# Microcontroller.net
KiCad netlist of a schematic drawn in Altium Designer
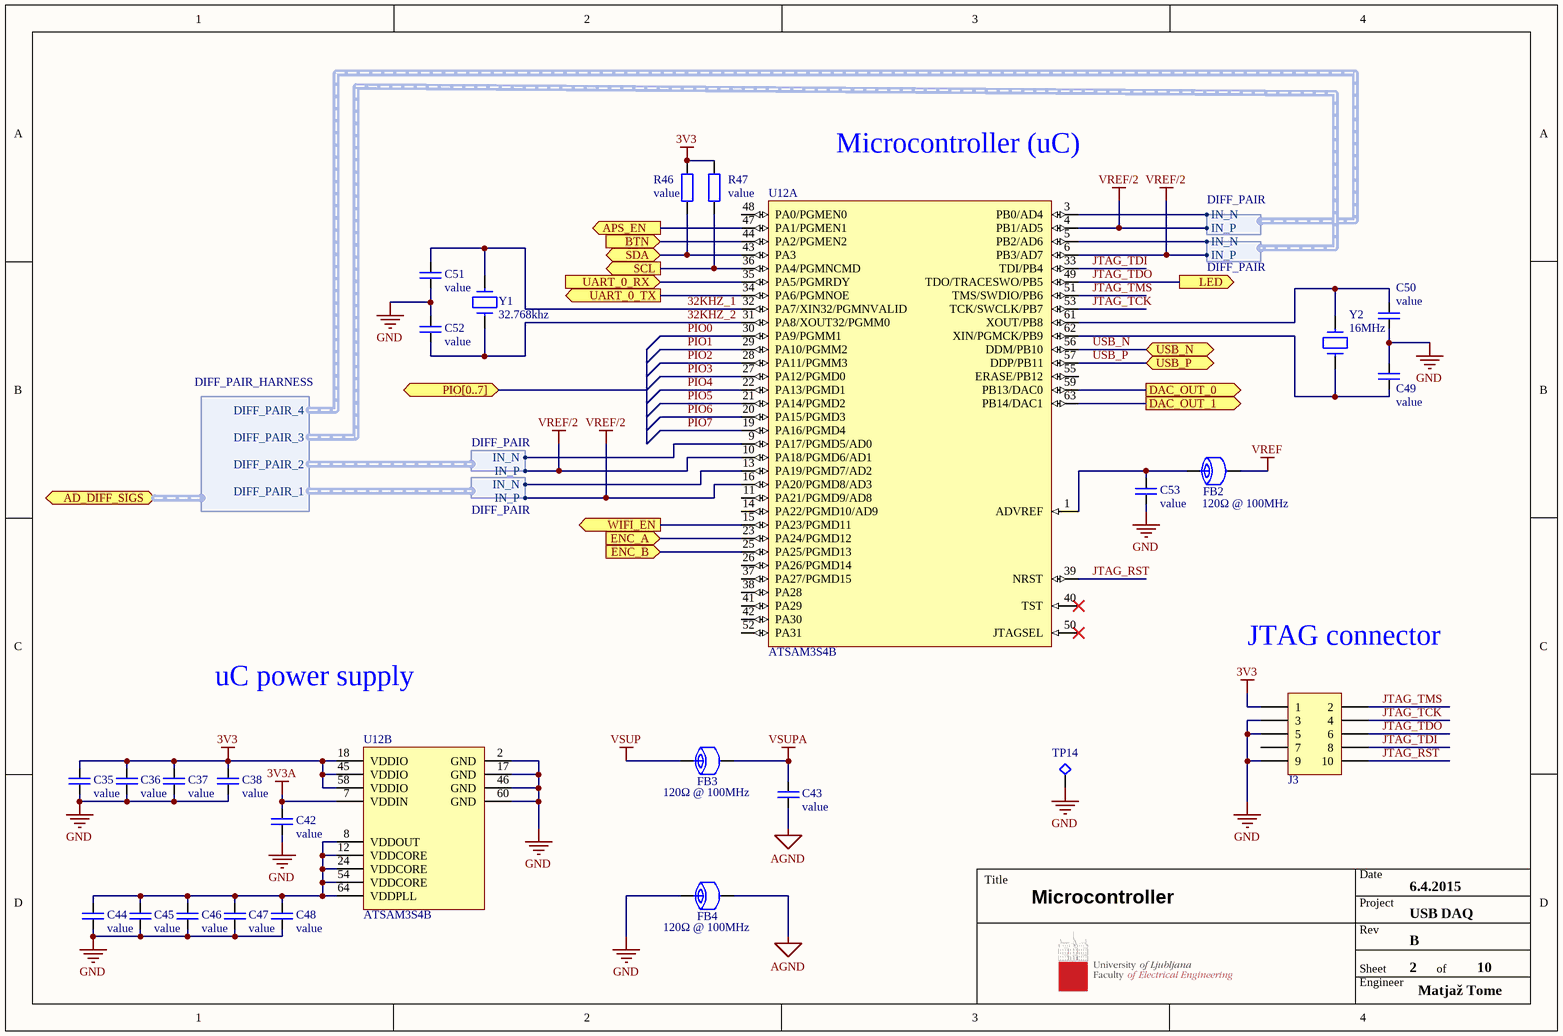
[diagram p0: Microcontroller.SchDoc]

(export (version "E")
  (design (tool "Eeschema 10.0.6"))
  (components
    (comp (ref "C35")
      (value "value")
      (footprint "C_0603")
      (description "Generic capacitor")
      (fields (field (name "Comment") "comment"))
      (libsource (lib "DAQ") (part "Capacitor"))
    )
    (comp (ref "C36")
      (value "value")
      (footprint "C_0603")
      (description "Generic capacitor")
      (fields (field (name "Comment") "comment"))
      (libsource (lib "DAQ") (part "Capacitor"))
    )
    (comp (ref "C37")
      (value "value")
      (footprint "C_0603")
      (description "Generic capacitor")
      (fields (field (name "Comment") "comment"))
      (libsource (lib "DAQ") (part "Capacitor"))
    )
    (comp (ref "C38")
      (value "value")
      (footprint "C_0603")
      (description "Generic capacitor")
      (fields (field (name "Comment") "comment"))
      (libsource (lib "DAQ") (part "Capacitor"))
    )
    (comp (ref "C42")
      (value "value")
      (footprint "C_0603")
      (description "Generic capacitor")
      (fields (field (name "Comment") "comment"))
      (libsource (lib "DAQ") (part "Capacitor"))
    )
    (comp (ref "C43")
      (value "value")
      (footprint "C_0603")
      (description "Generic capacitor")
      (fields (field (name "Comment") "comment"))
      (libsource (lib "DAQ") (part "Capacitor"))
    )
    (comp (ref "C44")
      (value "value")
      (footprint "C_0603")
      (description "Generic capacitor")
      (fields (field (name "Comment") "comment"))
      (libsource (lib "DAQ") (part "Capacitor"))
    )
    (comp (ref "C45")
      (value "value")
      (footprint "C_0603")
      (description "Generic capacitor")
      (fields (field (name "Comment") "comment"))
      (libsource (lib "DAQ") (part "Capacitor"))
    )
    (comp (ref "C46")
      (value "value")
      (footprint "C_0603")
      (description "Generic capacitor")
      (fields (field (name "Comment") "comment"))
      (libsource (lib "DAQ") (part "Capacitor"))
    )
    (comp (ref "C47")
      (value "value")
      (footprint "C_0603")
      (description "Generic capacitor")
      (fields (field (name "Comment") "comment"))
      (libsource (lib "DAQ") (part "Capacitor"))
    )
    (comp (ref "C48")
      (value "value")
      (footprint "C_0603")
      (description "Generic capacitor")
      (fields (field (name "Comment") "comment"))
      (libsource (lib "DAQ") (part "Capacitor"))
    )
    (comp (ref "C49")
      (value "value")
      (footprint "C_0603")
      (description "Generic capacitor")
      (fields (field (name "Comment") "comment"))
      (libsource (lib "DAQ") (part "Capacitor"))
    )
    (comp (ref "C50")
      (value "value")
      (footprint "C_0603")
      (description "Generic capacitor")
      (fields (field (name "Comment") "comment"))
      (libsource (lib "DAQ") (part "Capacitor"))
    )
    (comp (ref "C51")
      (value "value")
      (footprint "C_0603")
      (description "Generic capacitor")
      (fields (field (name "Comment") "comment"))
      (libsource (lib "DAQ") (part "Capacitor"))
    )
    (comp (ref "C52")
      (value "value")
      (footprint "C_0603")
      (description "Generic capacitor")
      (fields (field (name "Comment") "comment"))
      (libsource (lib "DAQ") (part "Capacitor"))
    )
    (comp (ref "C53")
      (value "value")
      (footprint "C_0603")
      (description "Generic capacitor")
      (fields (field (name "Comment") "comment"))
      (libsource (lib "DAQ") (part "Capacitor"))
    )
    (comp (ref "FB2")
      (value "120Ω @ 100MHz")
      (footprint "SMD_0805")
      (description "Ferrite Bead, 0805 [2012 Metric], 120 ohm, 800 mA, BLM21A Series, 0.15 ohm, ± 25%")
      (fields (field (name "MANUFACTURER") "Murata"))
      (libsource (lib "DAQ") (part "BLM21AG121SN1D"))
    )
    (comp (ref "FB3")
      (value "120Ω @ 100MHz")
      (footprint "SMD_0805")
      (description "Ferrite Bead, 0805 [2012 Metric], 120 ohm, 800 mA, BLM21A Series, 0.15 ohm, ± 25%")
      (fields (field (name "MANUFACTURER") "Murata"))
      (libsource (lib "DAQ") (part "BLM21AG121SN1D"))
    )
    (comp (ref "FB4")
      (value "120Ω @ 100MHz")
      (footprint "SMD_0805")
      (description "Ferrite Bead, 0805 [2012 Metric], 120 ohm, 800 mA, BLM21A Series, 0.15 ohm, ± 25%")
      (fields (field (name "MANUFACTURER") "Murata"))
      (libsource (lib "DAQ") (part "BLM21AG121SN1D"))
    )
    (comp (ref "J3")
      (value "M50-3600542")
      (footprint "HEADER_2X05_1.27mm")
      (description "Pin Header, Board-to-Board, 1.27 mm, 2 Rows, 10 Contacts, Surface Mount, Archer M50 Series")
      (fields (field (name "MANUFACTURER") "Harwin"))
      (libsource (lib "DAQ") (part "M50-3600542"))
    )
    (comp (ref "R46")
      (value "value")
      (footprint "R_0603")
      (description "Generic resistor")
      (fields (field (name "Comment") "comment"))
      (libsource (lib "DAQ") (part "Resistor"))
    )
    (comp (ref "R47")
      (value "value")
      (footprint "R_0603")
      (description "Generic resistor")
      (fields (field (name "Comment") "comment"))
      (libsource (lib "DAQ") (part "Resistor"))
    )
    (comp (ref "TP14")
      (value "test point 1.5mm")
      (footprint "TP1_FULL")
      (description "Test point ,1.5mm diameter, no hole")
      (libsource (lib "DAQ") (part "Test Point"))
    )
    (comp (ref "U12")
      (value "ATSAM3S4B")
      (footprint "LQFP64")
      (description "ARM MCU, SAM3S Series, SAM32 Family SAM 3S Series Microcontrollers, ARM Cortex-M3, 32bit, 64 MHz")
      (fields (field (name "MANUFACTURER") "Atmel"))
      (libsource (lib "DAQ") (part "ATSAM3SXB"))
    )
    (comp (ref "Y1")
      (value "32.768khz")
      (footprint "2X6_FLAT")
      (description "Crystal, 32.768 kHz, Cylinder Radial, 6.2mm x 2mm Dia, 12.5 pF, 20 ppm, R26 Series")
      (fields (field (name "PART NUMBER") "XCR0010") (field (name "MANUFACTURER") "RALTRON"))
      (libsource (lib "DAQ") (part "R26-32.768- 12.5"))
    )
    (comp (ref "Y2")
      (value "16MHz")
      (footprint "5X3.2")
      (description "Crystal, 16 MHz, SMD, 5mm x 3.2mm, 30 ppm, 18 pF, 30 ppm, 7A Series")
      (fields (field (name "MANUFACTURER") "TCX"))
      (libsource (lib "DAQ") (part "7A-16.000MAAJ-T"))
    )
  )
  (nets
    (net (code "3") (name "/32KHZ_1") (class "Default")
      (node (ref "C51") (pin "1") (pinfunction "1_1") (pintype "passive"))
      (node (ref "U12") (pin "32") (pinfunction "PA7/XIN32/PGMNVALID_32") (pintype "bidirectional"))
      (node (ref "Y1") (pin "2") (pinfunction "2_2") (pintype "passive"))
    )
    (net (code "4") (name "/32KHZ_2") (class "Default")
      (node (ref "C52") (pin "1") (pinfunction "1_1") (pintype "passive"))
      (node (ref "U12") (pin "31") (pinfunction "PA8/XOUT32/PGMM0_31") (pintype "bidirectional"))
      (node (ref "Y1") (pin "1") (pinfunction "1_1") (pintype "passive"))
    )
    (net (code "5") (name "/APS_EN") (class "Default")
      (node (ref "U12") (pin "47") (pinfunction "PA1/PGMEN1_47") (pintype "bidirectional"))
    )
    (net (code "6") (name "/BTN") (class "Default")
      (node (ref "U12") (pin "44") (pinfunction "PA2/PGMEN2_44") (pintype "bidirectional"))
    )
    (net (code "7") (name "/DAC_OUT_0") (class "Default")
      (node (ref "U12") (pin "59") (pinfunction "PB13/DAC0_59") (pintype "bidirectional"))
    )
    (net (code "8") (name "/DAC_OUT_1") (class "Default")
      (node (ref "U12") (pin "63") (pinfunction "PB14/DAC1_63") (pintype "bidirectional"))
    )
    (net (code "9") (name "/ENC_A") (class "Default")
      (node (ref "U12") (pin "23") (pinfunction "PA24/PGMD12_23") (pintype "bidirectional"))
    )
    (net (code "10") (name "/ENC_B") (class "Default")
      (node (ref "U12") (pin "25") (pinfunction "PA25/PGMD13_25") (pintype "bidirectional"))
    )
    (net (code "11") (name "/JTAG_RST") (class "Default")
      (node (ref "J3") (pin "10") (pinfunction "10_10") (pintype "passive"))
      (node (ref "U12") (pin "39") (pinfunction "NRST_39") (pintype "bidirectional"))
    )
    (net (code "12") (name "/JTAG_TCK") (class "Default")
      (node (ref "J3") (pin "4") (pinfunction "4_4") (pintype "passive"))
      (node (ref "U12") (pin "53") (pinfunction "TCK/SWCLK/PB7_53") (pintype "bidirectional"))
    )
    (net (code "13") (name "/JTAG_TDI") (class "Default")
      (node (ref "J3") (pin "8") (pinfunction "8_8") (pintype "passive"))
      (node (ref "U12") (pin "33") (pinfunction "TDI/PB4_33") (pintype "bidirectional"))
    )
    (net (code "14") (name "/JTAG_TDO") (class "Default")
      (node (ref "J3") (pin "6") (pinfunction "6_6") (pintype "passive"))
      (node (ref "U12") (pin "49") (pinfunction "TDO/TRACESWO/PB5_49") (pintype "bidirectional"))
    )
    (net (code "15") (name "/JTAG_TMS") (class "Default")
      (node (ref "J3") (pin "2") (pinfunction "2_2") (pintype "passive"))
      (node (ref "U12") (pin "51") (pinfunction "TMS/SWDIO/PB6_51") (pintype "bidirectional"))
    )
    (net (code "16") (name "/PIO0") (class "Default")
      (node (ref "U12") (pin "30") (pinfunction "PA9/PGMM1_30") (pintype "bidirectional"))
    )
    (net (code "17") (name "/PIO1") (class "Default")
      (node (ref "U12") (pin "29") (pinfunction "PA10/PGMM2_29") (pintype "bidirectional"))
    )
    (net (code "18") (name "/PIO2") (class "Default")
      (node (ref "U12") (pin "28") (pinfunction "PA11/PGMM3_28") (pintype "bidirectional"))
    )
    (net (code "19") (name "/PIO3") (class "Default")
      (node (ref "U12") (pin "27") (pinfunction "PA12/PGMD0_27") (pintype "bidirectional"))
    )
    (net (code "20") (name "/PIO4") (class "Default")
      (node (ref "U12") (pin "22") (pinfunction "PA13/PGMD1_22") (pintype "bidirectional"))
    )
    (net (code "21") (name "/PIO5") (class "Default")
      (node (ref "U12") (pin "21") (pinfunction "PA14/PGMD2_21") (pintype "bidirectional"))
    )
    (net (code "22") (name "/PIO6") (class "Default")
      (node (ref "U12") (pin "20") (pinfunction "PA15/PGMD3_20") (pintype "bidirectional"))
    )
    (net (code "23") (name "/PIO7") (class "Default")
      (node (ref "U12") (pin "19") (pinfunction "PA16/PGMD4_19") (pintype "bidirectional"))
    )
    (net (code "25") (name "/SCL") (class "Default")
      (node (ref "R47") (pin "1") (pintype "passive"))
      (node (ref "U12") (pin "36") (pinfunction "PA4/PGMNCMD_36") (pintype "bidirectional"))
    )
    (net (code "26") (name "/SDA") (class "Default")
      (node (ref "R46") (pin "1") (pintype "passive"))
      (node (ref "U12") (pin "43") (pinfunction "PA3_43") (pintype "bidirectional"))
    )
    (net (code "27") (name "/UART_0_RX") (class "Default")
      (node (ref "U12") (pin "35") (pinfunction "PA5/PGMRDY_35") (pintype "bidirectional"))
    )
    (net (code "28") (name "/UART_0_TX") (class "Default")
      (node (ref "U12") (pin "34") (pinfunction "PA6/PGMNOE_34") (pintype "bidirectional"))
    )
    (net (code "29") (name "/USB_N") (class "Default")
      (node (ref "U12") (pin "56") (pinfunction "DDM/PB10_56") (pintype "bidirectional"))
    )
    (net (code "30") (name "/USB_P") (class "Default")
      (node (ref "U12") (pin "57") (pinfunction "DDP/PB11_57") (pintype "bidirectional"))
    )
    (net (code "31") (name "/WIFI_EN") (class "Default")
      (node (ref "U12") (pin "15") (pinfunction "PA23/PGMD11_15") (pintype "bidirectional"))
    )
    (net (code "34") (name "3V3") (class "Default")
      (node (ref "C35") (pin "1") (pinfunction "1_1") (pintype "passive"))
      (node (ref "C36") (pin "1") (pinfunction "1_1") (pintype "passive"))
      (node (ref "C37") (pin "1") (pinfunction "1_1") (pintype "passive"))
      (node (ref "C38") (pin "1") (pinfunction "1_1") (pintype "passive"))
      (node (ref "J3") (pin "1") (pinfunction "1_1") (pintype "passive"))
      (node (ref "R46") (pin "2") (pintype "passive"))
      (node (ref "R47") (pin "2") (pintype "passive"))
      (node (ref "U12") (pin "18") (pinfunction "VDDIO_18") (pintype "power_in"))
      (node (ref "U12") (pin "45") (pinfunction "VDDIO_45") (pintype "power_in"))
      (node (ref "U12") (pin "58") (pinfunction "VDDIO_58") (pintype "power_in"))
    )
    (net (code "35") (name "3V3A") (class "Default")
      (node (ref "C42") (pin "1") (pinfunction "1_1") (pintype "passive"))
      (node (ref "U12") (pin "7") (pinfunction "VDDIN_7") (pintype "power_in"))
    )
    (net (code "36") (name "AGND") (class "Default")
      (node (ref "C43") (pin "2") (pinfunction "2_2") (pintype "passive"))
      (node (ref "FB4") (pin "2") (pintype "passive"))
    )
    (net (code "37") (name "GND") (class "Default")
      (node (ref "C35") (pin "2") (pinfunction "2_2") (pintype "passive"))
      (node (ref "C36") (pin "2") (pinfunction "2_2") (pintype "passive"))
      (node (ref "C37") (pin "2") (pinfunction "2_2") (pintype "passive"))
      (node (ref "C38") (pin "2") (pinfunction "2_2") (pintype "passive"))
      (node (ref "C42") (pin "2") (pinfunction "2_2") (pintype "passive"))
      (node (ref "C44") (pin "2") (pinfunction "2_2") (pintype "passive"))
      (node (ref "C45") (pin "2") (pinfunction "2_2") (pintype "passive"))
      (node (ref "C46") (pin "2") (pinfunction "2_2") (pintype "passive"))
      (node (ref "C47") (pin "2") (pinfunction "2_2") (pintype "passive"))
      (node (ref "C48") (pin "2") (pinfunction "2_2") (pintype "passive"))
      (node (ref "C49") (pin "2") (pinfunction "2_2") (pintype "passive"))
      (node (ref "C50") (pin "2") (pinfunction "2_2") (pintype "passive"))
      (node (ref "C51") (pin "2") (pinfunction "2_2") (pintype "passive"))
      (node (ref "C52") (pin "2") (pinfunction "2_2") (pintype "passive"))
      (node (ref "C53") (pin "2") (pinfunction "2_2") (pintype "passive"))
      (node (ref "FB4") (pin "1") (pintype "passive"))
      (node (ref "J3") (pin "3") (pinfunction "3_3") (pintype "passive"))
      (node (ref "J3") (pin "5") (pinfunction "5_5") (pintype "passive"))
      (node (ref "J3") (pin "9") (pinfunction "9_9") (pintype "passive"))
      (node (ref "TP14") (pin "1") (pinfunction "1_1") (pintype "passive"))
      (node (ref "U12") (pin "17") (pinfunction "GND_17") (pintype "power_in"))
      (node (ref "U12") (pin "2") (pinfunction "GND_2") (pintype "power_in"))
      (node (ref "U12") (pin "46") (pinfunction "GND_46") (pintype "power_in"))
      (node (ref "U12") (pin "60") (pinfunction "GND_60") (pintype "power_in"))
    )
    (net (code "38") (name "Net-(U12A-ADVREF)") (class "Default")
      (node (ref "C53") (pin "1") (pinfunction "1_1") (pintype "passive"))
      (node (ref "FB2") (pin "1") (pintype "passive"))
      (node (ref "U12") (pin "1") (pinfunction "ADVREF_1") (pintype "input"))
    )
    (net (code "39") (name "Net-(U12A-XIN{slash}PGMCK{slash}PB9)") (class "Default")
      (node (ref "C49") (pin "1") (pinfunction "1_1") (pintype "passive"))
      (node (ref "U12") (pin "62") (pinfunction "XIN/PGMCK/PB9_62") (pintype "bidirectional"))
      (node (ref "Y2") (pin "1") (pinfunction "1_1") (pintype "passive"))
    )
    (net (code "40") (name "Net-(U12A-XOUT{slash}PB8)") (class "Default")
      (node (ref "C50") (pin "1") (pinfunction "1_1") (pintype "passive"))
      (node (ref "U12") (pin "61") (pinfunction "XOUT/PB8_61") (pintype "bidirectional"))
      (node (ref "Y2") (pin "2") (pinfunction "2_2") (pintype "passive"))
    )
    (net (code "41") (name "Net-(U12B-VDDOUT)") (class "Default")
      (node (ref "C44") (pin "1") (pinfunction "1_1") (pintype "passive"))
      (node (ref "C45") (pin "1") (pinfunction "1_1") (pintype "passive"))
      (node (ref "C46") (pin "1") (pinfunction "1_1") (pintype "passive"))
      (node (ref "C47") (pin "1") (pinfunction "1_1") (pintype "passive"))
      (node (ref "C48") (pin "1") (pinfunction "1_1") (pintype "passive"))
      (node (ref "U12") (pin "12") (pinfunction "VDDCORE_12") (pintype "power_in"))
      (node (ref "U12") (pin "24") (pinfunction "VDDCORE_24") (pintype "power_in"))
      (node (ref "U12") (pin "54") (pinfunction "VDDCORE_54") (pintype "power_in"))
      (node (ref "U12") (pin "64") (pinfunction "VDDPLL_64") (pintype "power_in"))
      (node (ref "U12") (pin "8") (pinfunction "VDDOUT_8") (pintype "power_in"))
    )
    (net (code "42") (name "VREF") (class "Default") (node (ref "FB2") (pin "2") (pintype "passive")))
    (net (code "43") (name "VREF{slash}2") (class "Default")
      (node (ref "U12") (pin "10") (pinfunction "PA18/PGMD6/AD1_10") (pintype "bidirectional"))
      (node (ref "U12") (pin "16") (pinfunction "PA20/PGMD8/AD3_16") (pintype "bidirectional"))
      (node (ref "U12") (pin "4") (pinfunction "PB1/AD5_4") (pintype "bidirectional"))
      (node (ref "U12") (pin "6") (pinfunction "PB3/AD7_6") (pintype "bidirectional"))
    )
    (net (code "44") (name "VSUP") (class "Default") (node (ref "FB3") (pin "1") (pintype "passive")))
    (net (code "45") (name "VSUPA") (class "Default")
      (node (ref "C43") (pin "1") (pinfunction "1_1") (pintype "passive"))
      (node (ref "FB3") (pin "2") (pintype "passive"))
    )
    (net (code "46") (name "unconnected-(J3-Pad7)") (class "Default")
      (node (ref "J3") (pin "7") (pinfunction "7_7") (pintype "passive"))
    )
    (net (code "47") (name "unconnected-(U12A-ERASE{slash}PB12-Pad55)") (class "Default")
      (node (ref "U12") (pin "55") (pinfunction "ERASE/PB12_55") (pintype "bidirectional"))
    )
    (net (code "48") (name "unconnected-(U12A-JTAGSEL-Pad50)") (class "Default")
      (node (ref "U12") (pin "50") (pinfunction "JTAGSEL_50") (pintype "input+no_connect"))
    )
    (net (code "49") (name "unconnected-(U12A-PA0{slash}PGMEN0-Pad48)") (class "Default")
      (node (ref "U12") (pin "48") (pinfunction "PA0/PGMEN0_48") (pintype "bidirectional"))
    )
    (net (code "50") (name "unconnected-(U12A-PA17{slash}PGMD5{slash}AD0-Pad9)") (class "Default")
      (node (ref "U12") (pin "9") (pinfunction "PA17/PGMD5/AD0_9") (pintype "bidirectional"))
    )
    (net (code "51") (name "unconnected-(U12A-PA19{slash}PGMD7{slash}AD2-Pad13)") (class "Default")
      (node (ref "U12") (pin "13") (pinfunction "PA19/PGMD7/AD2_13") (pintype "bidirectional"))
    )
    (net (code "52") (name "unconnected-(U12A-PA21{slash}PGMD9{slash}AD8-Pad11)") (class "Default")
      (node (ref "U12") (pin "11") (pinfunction "PA21/PGMD9/AD8_11") (pintype "bidirectional"))
    )
    (net (code "53") (name "unconnected-(U12A-PA22{slash}PGMD10{slash}AD9-Pad14)") (class "Default")
      (node (ref "U12") (pin "14") (pinfunction "PA22/PGMD10/AD9_14") (pintype "bidirectional"))
    )
    (net (code "54") (name "unconnected-(U12A-PA26{slash}PGMD14-Pad26)") (class "Default")
      (node (ref "U12") (pin "26") (pinfunction "PA26/PGMD14_26") (pintype "bidirectional"))
    )
    (net (code "55") (name "unconnected-(U12A-PA27{slash}PGMD15-Pad37)") (class "Default")
      (node (ref "U12") (pin "37") (pinfunction "PA27/PGMD15_37") (pintype "bidirectional"))
    )
    (net (code "56") (name "unconnected-(U12A-PA28-Pad38)") (class "Default")
      (node (ref "U12") (pin "38") (pinfunction "PA28_38") (pintype "bidirectional"))
    )
    (net (code "57") (name "unconnected-(U12A-PA29-Pad41)") (class "Default")
      (node (ref "U12") (pin "41") (pinfunction "PA29_41") (pintype "bidirectional"))
    )
    (net (code "58") (name "unconnected-(U12A-PA30-Pad42)") (class "Default")
      (node (ref "U12") (pin "42") (pinfunction "PA30_42") (pintype "bidirectional"))
    )
    (net (code "59") (name "unconnected-(U12A-PA31-Pad52)") (class "Default")
      (node (ref "U12") (pin "52") (pinfunction "PA31_52") (pintype "bidirectional"))
    )
    (net (code "60") (name "unconnected-(U12A-PB0{slash}AD4-Pad3)") (class "Default")
      (node (ref "U12") (pin "3") (pinfunction "PB0/AD4_3") (pintype "bidirectional"))
    )
    (net (code "61") (name "unconnected-(U12A-PB2{slash}AD6-Pad5)") (class "Default")
      (node (ref "U12") (pin "5") (pinfunction "PB2/AD6_5") (pintype "bidirectional"))
    )
    (net (code "62") (name "unconnected-(U12A-TST-Pad40)") (class "Default")
      (node (ref "U12") (pin "40") (pinfunction "TST_40") (pintype "input+no_connect"))
    )
  )
)
